# 08_CoreBoard.net
KiCad netlist of a schematic drawn in Altium Designer
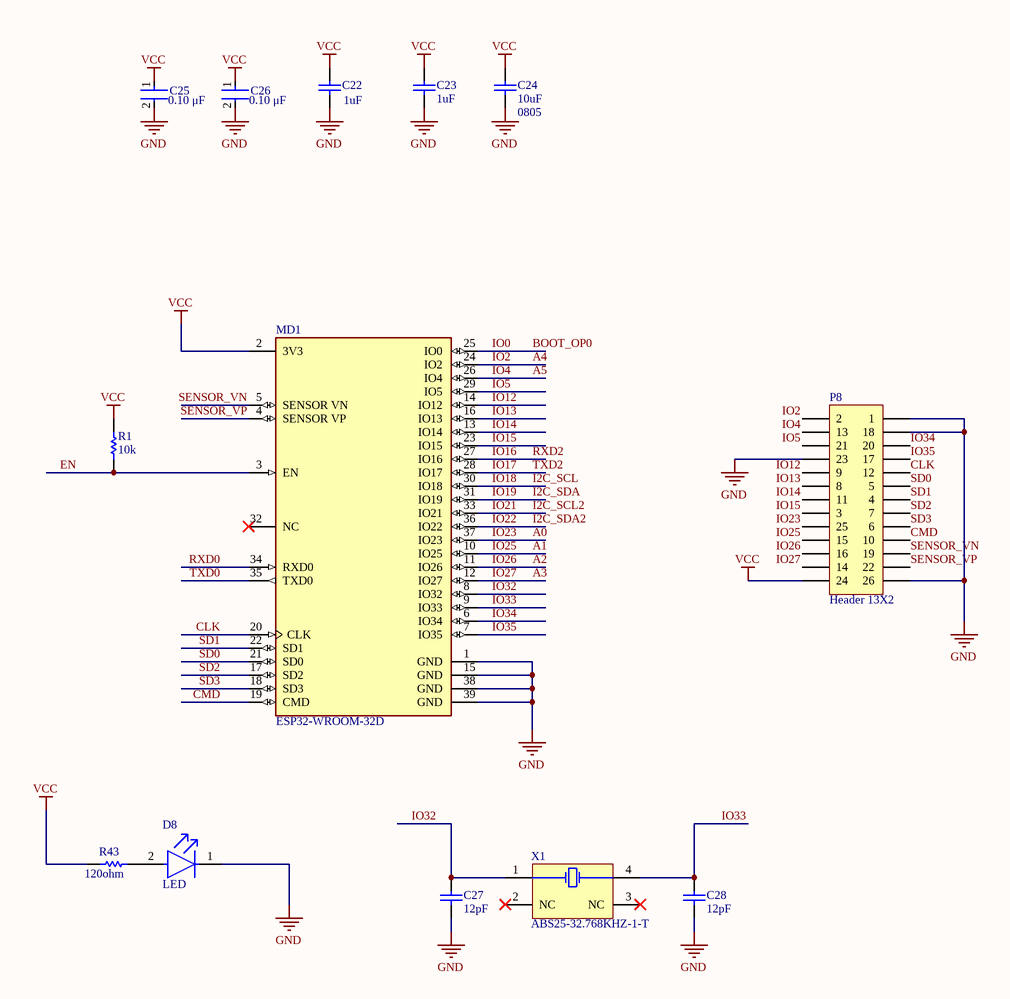
[diagram p0: 08_CoreBoard.SchDoc]

(export (version "E")
  (design (tool "Eeschema 10.0.6"))
  (components
    (comp (ref "C22")
      (value "1uF")
      (footprint "CAPC1608X87X35LL15T15")
      (fields
        (field (name "MANUFACTURER") "Kemet")
        (field (name "PART NUMBER") "C0603C101J1GACTU")
        (field (name "Comment") "C0603_1UF")
      )
      (libsource (lib "Altium Content Vault") (part "CAP"))
    )
    (comp (ref "C23")
      (value "1uF")
      (footprint "CAPC1608X87X35LL15T15")
      (fields
        (field (name "MANUFACTURER") "Kemet")
        (field (name "PART NUMBER") "C0603C101J1GACTU")
        (field (name "Comment") "C0603_1UF")
      )
      (libsource (lib "Altium Content Vault") (part "CAP"))
    )
    (comp (ref "C24")
      (value "10uF")
      (footprint "CAPC2013X135X50LL10T20")
      (fields
        (field (name "MANUFACTURER") "Murata")
        (field (name "PART NUMBER") "GRM21BR61C106KE15L")
        (field (name "PACKAGE") "0805")
        (field (name "Comment") "C0805_10UF")
      )
      (libsource (lib "Altium Content Vault") (part "CAP"))
    )
    (comp (ref "C25")
      (value "C0603_0.1UF")
      (footprint "FP-C0603C-CF-MFG")
      (description "CAP CER 0.1UF 16V X7R 0603")
      (fields
        (field (name "TOLERANCE") "0.2")
        (field (name "CAPACITANCE") "0.10 μF")
        (field (name "MANUFACTURER PART NUMBER") "C0603C104M4RAC7411")
      )
      (libsource (lib "Altium Content Vault") (part "b4654b650e69147ec39a6b967a45e02"))
    )
    (comp (ref "C26")
      (value "C0603_0.1UF")
      (footprint "FP-C0603C-CF-MFG")
      (description "CAP CER 0.1UF 16V X7R 0603")
      (fields
        (field (name "TOLERANCE") "0.2")
        (field (name "CAPACITANCE") "0.10 μF")
        (field (name "MANUFACTURER PART NUMBER") "C0603C104M4RAC7411")
      )
      (libsource (lib "Altium Content Vault") (part "b4654b650e69147ec39a6b967a45e02"))
    )
    (comp (ref "C27")
      (value "12pF")
      (footprint "CAPC1608X90X40NL10T20")
      (description "Chip Capacitor, 12 pF, +/- 5%, 50 V, -55 to 125 degC, 0603 (1608 Metric), RoHS, Tape and Reel")
      (fields (field (name "TOLERANCE") "1%") (field (name "Comment") "CC0603JRNPO9BN120"))
      (libsource (lib "Altium Content Vault") (part "CAP-NP-2"))
    )
    (comp (ref "C28")
      (value "12pF")
      (footprint "CAPC1608X90X40NL10T20")
      (description "Chip Capacitor, 12 pF, +/- 5%, 50 V, -55 to 125 degC, 0603 (1608 Metric), RoHS, Tape and Reel")
      (fields (field (name "TOLERANCE") "1%") (field (name "Comment") "CC0603JRNPO9BN120"))
      (libsource (lib "Altium Content Vault") (part "CAP-NP-2"))
    )
    (comp (ref "D8")
      (value "LED")
      (footprint "FP-LTST-C190GKT-MFG")
      (description "LED GREEN CLEAR CHIP SMD")
      (fields (field (name "VOLTAGE") "2V"))
      (libsource (lib "Altium Content Vault") (part "8706943c75ba83719d021d2fdc84c58"))
    )
    (comp (ref "MD1")
      (value "ESP32-WROOM-32D")
      (footprint "FP-ESP32-WROOM-32D-MFG")
      (description "WIFI MODULE 32MBITS SPI FLASH")
      (fields
        (field (name "OCTOPART") "https://octopart.com/esp32-wroom-32d-espressif+systems-91040050")
        (field (name "MANUFACTURER") "Espressif Systems")
      )
      (libsource (lib "Altium Content Vault") (part "a031a76f8c27026a7a7f4657ff233a3"))
    )
    (comp (ref "P8")
      (value "Header 13X2")
      (footprint "HDR2X13")
      (description "Header, 13-Pin, Dual row")
      (fields (field (name "PUBLISHER") "Altium Limited"))
      (libsource (lib "Miscellaneous Connectors") (part "Header 13X2"))
    )
    (comp (ref "R1")
      (value "10k")
      (footprint "RESC1609X55X30LL15T15")
      (description "Chip Resistor, 10 KOhm, +/- 1%, 0.1 W, -55 to 155 degC, 0603 (1608 Metric), RoHS, Tape and Reel")
      (fields (field (name "TOLERANCE") "1%") (field (name "MANUFACTURER") "Panasonic"))
      (libsource (lib "Altium Content Vault") (part "RES-2"))
    )
    (comp (ref "R43")
      (value "120ohm")
      (footprint "RESC1608X55X30NL20T20")
      (fields
        (field (name "PART NUMBER") "ERA-3AEB121V")
        (field (name "MANUFACTURER") "Panasonic")
        (field (name "Comment") "R0603_120R")
      )
      (libsource (lib "Altium Content Vault") (part "RES"))
    )
    (comp (ref "X1")
      (value "ABS25-32.768KHZ-1-T")
      (footprint "ABRA-ABS25-4_V")
      (description "Low Frequency Crystal, 32.768 KHz, -40 to 85 degC, 4-Pin SMD, RoHS, Tape and Reel")
      (fields (field (name "MANUFACTURER") "ABRACON") (field (name "TOLERANCE") "10PPM"))
      (libsource (lib "Altium Content Vault") (part "XTAL-1-4-4_A"))
    )
  )
  (nets
    (net (code "1") (name "/A0") (class "Default")
      (node (ref "MD1") (pin "37") (pinfunction "IO23_37") (pintype "bidirectional"))
      (node (ref "P8") (pin "25") (pinfunction "25_25") (pintype "passive"))
    )
    (net (code "2") (name "/A1") (class "Default")
      (node (ref "MD1") (pin "10") (pinfunction "IO25_10") (pintype "bidirectional"))
      (node (ref "P8") (pin "15") (pinfunction "15_15") (pintype "passive"))
    )
    (net (code "3") (name "/A2") (class "Default")
      (node (ref "MD1") (pin "11") (pinfunction "IO26_11") (pintype "bidirectional"))
      (node (ref "P8") (pin "16") (pinfunction "16_16") (pintype "passive"))
    )
    (net (code "4") (name "/A3") (class "Default")
      (node (ref "MD1") (pin "12") (pinfunction "IO27_12") (pintype "bidirectional"))
      (node (ref "P8") (pin "14") (pinfunction "14_14") (pintype "passive"))
    )
    (net (code "5") (name "/A4") (class "Default")
      (node (ref "MD1") (pin "24") (pinfunction "IO2_24") (pintype "bidirectional"))
      (node (ref "P8") (pin "2") (pinfunction "2_2") (pintype "passive"))
    )
    (net (code "6") (name "/A5") (class "Default")
      (node (ref "MD1") (pin "26") (pinfunction "IO4_26") (pintype "bidirectional"))
      (node (ref "P8") (pin "13") (pinfunction "13_13") (pintype "passive"))
    )
    (net (code "7") (name "/BOOT_OP0") (class "Default")
      (node (ref "MD1") (pin "25") (pinfunction "IO0_25") (pintype "bidirectional"))
    )
    (net (code "8") (name "/CLK") (class "Default")
      (node (ref "MD1") (pin "20") (pinfunction "CLK_20") (pintype "input"))
      (node (ref "P8") (pin "12") (pinfunction "12_12") (pintype "passive"))
    )
    (net (code "9") (name "/CMD") (class "Default")
      (node (ref "MD1") (pin "19") (pinfunction "CMD_19") (pintype "bidirectional"))
      (node (ref "P8") (pin "10") (pinfunction "10_10") (pintype "passive"))
    )
    (net (code "10") (name "/EN") (class "Default")
      (node (ref "MD1") (pin "3") (pinfunction "EN_3") (pintype "input"))
      (node (ref "R1") (pin "2") (pinfunction "2_2") (pintype "passive"))
    )
    (net (code "11") (name "/I2C_SCL") (class "Default")
      (node (ref "MD1") (pin "30") (pinfunction "IO18_30") (pintype "bidirectional"))
    )
    (net (code "12") (name "/I2C_SCL2") (class "Default")
      (node (ref "MD1") (pin "33") (pinfunction "IO21_33") (pintype "bidirectional"))
    )
    (net (code "13") (name "/I2C_SDA") (class "Default")
      (node (ref "MD1") (pin "31") (pinfunction "IO19_31") (pintype "bidirectional"))
    )
    (net (code "14") (name "/I2C_SDA2") (class "Default")
      (node (ref "MD1") (pin "36") (pinfunction "IO22_36") (pintype "bidirectional"))
    )
    (net (code "15") (name "/IO5") (class "Default")
      (node (ref "MD1") (pin "29") (pinfunction "IO5_29") (pintype "bidirectional"))
      (node (ref "P8") (pin "21") (pinfunction "21_21") (pintype "passive"))
    )
    (net (code "16") (name "/IO12") (class "Default")
      (node (ref "MD1") (pin "14") (pinfunction "IO12_14") (pintype "bidirectional"))
      (node (ref "P8") (pin "9") (pinfunction "9_9") (pintype "passive"))
    )
    (net (code "17") (name "/IO13") (class "Default")
      (node (ref "MD1") (pin "16") (pinfunction "IO13_16") (pintype "bidirectional"))
      (node (ref "P8") (pin "8") (pinfunction "8_8") (pintype "passive"))
    )
    (net (code "18") (name "/IO14") (class "Default")
      (node (ref "MD1") (pin "13") (pinfunction "IO14_13") (pintype "bidirectional"))
      (node (ref "P8") (pin "11") (pinfunction "11_11") (pintype "passive"))
    )
    (net (code "19") (name "/IO15") (class "Default")
      (node (ref "MD1") (pin "23") (pinfunction "IO15_23") (pintype "bidirectional"))
      (node (ref "P8") (pin "3") (pinfunction "3_3") (pintype "passive"))
    )
    (net (code "20") (name "/IO16") (class "Default")
      (node (ref "MD1") (pin "27") (pinfunction "IO16_27") (pintype "bidirectional"))
    )
    (net (code "21") (name "/IO17") (class "Default")
      (node (ref "MD1") (pin "28") (pinfunction "IO17_28") (pintype "bidirectional"))
    )
    (net (code "22") (name "/IO32") (class "Default")
      (node (ref "C27") (pin "2") (pinfunction "2_2") (pintype "passive"))
      (node (ref "MD1") (pin "8") (pinfunction "IO32_8") (pintype "bidirectional"))
      (node (ref "X1") (pin "1") (pinfunction "X1_1") (pintype "passive"))
    )
    (net (code "23") (name "/IO33") (class "Default")
      (node (ref "C28") (pin "2") (pinfunction "2_2") (pintype "passive"))
      (node (ref "MD1") (pin "9") (pinfunction "IO33_9") (pintype "bidirectional"))
      (node (ref "X1") (pin "4") (pinfunction "X2_4") (pintype "passive"))
    )
    (net (code "24") (name "/IO34") (class "Default")
      (node (ref "MD1") (pin "6") (pinfunction "IO34_6") (pintype "bidirectional"))
      (node (ref "P8") (pin "20") (pinfunction "20_20") (pintype "passive"))
    )
    (net (code "25") (name "/IO35") (class "Default")
      (node (ref "MD1") (pin "7") (pinfunction "IO35_7") (pintype "bidirectional"))
      (node (ref "P8") (pin "17") (pinfunction "17_17") (pintype "passive"))
    )
    (net (code "26") (name "/RXD0") (class "Default")
      (node (ref "MD1") (pin "34") (pinfunction "RXD0_34") (pintype "input"))
    )
    (net (code "27") (name "/SD0") (class "Default")
      (node (ref "MD1") (pin "21") (pinfunction "SD0_21") (pintype "bidirectional"))
      (node (ref "P8") (pin "5") (pinfunction "5_5") (pintype "passive"))
    )
    (net (code "28") (name "/SD1") (class "Default")
      (node (ref "MD1") (pin "22") (pinfunction "SD1_22") (pintype "bidirectional"))
      (node (ref "P8") (pin "4") (pinfunction "4_4") (pintype "passive"))
    )
    (net (code "29") (name "/SD2") (class "Default")
      (node (ref "MD1") (pin "17") (pinfunction "SD2_17") (pintype "bidirectional"))
      (node (ref "P8") (pin "7") (pinfunction "7_7") (pintype "passive"))
    )
    (net (code "30") (name "/SD3") (class "Default")
      (node (ref "MD1") (pin "18") (pinfunction "SD3_18") (pintype "bidirectional"))
      (node (ref "P8") (pin "6") (pinfunction "6_6") (pintype "passive"))
    )
    (net (code "31") (name "/SENSOR_VN") (class "Default")
      (node (ref "MD1") (pin "5") (pinfunction "SENSOR_VN_5") (pintype "bidirectional"))
      (node (ref "P8") (pin "19") (pinfunction "19_19") (pintype "passive"))
    )
    (net (code "32") (name "/SENSOR_VP") (class "Default")
      (node (ref "MD1") (pin "4") (pinfunction "SENSOR_VP_4") (pintype "bidirectional"))
      (node (ref "P8") (pin "22") (pinfunction "22_22") (pintype "passive"))
    )
    (net (code "33") (name "/TXD0") (class "Default")
      (node (ref "MD1") (pin "35") (pinfunction "TXD0_35") (pintype "output"))
    )
    (net (code "34") (name "GND") (class "Default")
      (node (ref "C22") (pin "1") (pinfunction "1_1") (pintype "passive"))
      (node (ref "C23") (pin "1") (pinfunction "1_1") (pintype "passive"))
      (node (ref "C24") (pin "1") (pinfunction "1_1") (pintype "passive"))
      (node (ref "C25") (pin "2") (pinfunction "2_2") (pintype "passive"))
      (node (ref "C26") (pin "2") (pinfunction "2_2") (pintype "passive"))
      (node (ref "C27") (pin "1") (pinfunction "1_1") (pintype "passive"))
      (node (ref "C28") (pin "1") (pinfunction "1_1") (pintype "passive"))
      (node (ref "D8") (pin "1") (pinfunction "C_1") (pintype "passive"))
      (node (ref "MD1") (pin "1") (pinfunction "GND_1") (pintype "power_in"))
      (node (ref "MD1") (pin "15") (pinfunction "GND_15") (pintype "power_in"))
      (node (ref "MD1") (pin "38") (pinfunction "GND_38") (pintype "power_in"))
      (node (ref "MD1") (pin "39") (pinfunction "GND_39") (pintype "power_in"))
      (node (ref "P8") (pin "1") (pinfunction "1_1") (pintype "passive"))
      (node (ref "P8") (pin "18") (pinfunction "18_18") (pintype "passive"))
      (node (ref "P8") (pin "23") (pinfunction "23_23") (pintype "passive"))
      (node (ref "P8") (pin "26") (pinfunction "26_26") (pintype "passive"))
    )
    (net (code "35") (name "Net-(D8-A)") (class "Default")
      (node (ref "D8") (pin "2") (pinfunction "A_2") (pintype "passive"))
      (node (ref "R43") (pin "2") (pinfunction "2_2") (pintype "passive"))
    )
    (net (code "36") (name "VCC") (class "Default")
      (node (ref "C22") (pin "2") (pinfunction "2_2") (pintype "passive"))
      (node (ref "C23") (pin "2") (pinfunction "2_2") (pintype "passive"))
      (node (ref "C24") (pin "2") (pinfunction "2_2") (pintype "passive"))
      (node (ref "C25") (pin "1") (pinfunction "1_1") (pintype "passive"))
      (node (ref "C26") (pin "1") (pinfunction "1_1") (pintype "passive"))
      (node (ref "MD1") (pin "2") (pinfunction "3V3_2") (pintype "power_in"))
      (node (ref "P8") (pin "24") (pinfunction "24_24") (pintype "passive"))
      (node (ref "R1") (pin "1") (pinfunction "1_1") (pintype "passive"))
      (node (ref "R43") (pin "1") (pinfunction "1_1") (pintype "passive"))
    )
    (net (code "37") (name "unconnected-(MD1-NC-Pad32)") (class "Default")
      (node (ref "MD1") (pin "32") (pinfunction "NC_32") (pintype "passive+no_connect"))
    )
    (net (code "38") (name "unconnected-(X1-NC-Pad2)") (class "Default")
      (node (ref "X1") (pin "2") (pinfunction "NC_2") (pintype "passive+no_connect"))
    )
    (net (code "39") (name "unconnected-(X1-NC-Pad3)") (class "Default")
      (node (ref "X1") (pin "3") (pinfunction "NC_3") (pintype "passive+no_connect"))
    )
  )
)
